# stm32f030f4p6_breakout.net
KiCad netlist of a schematic drawn in EAGLE
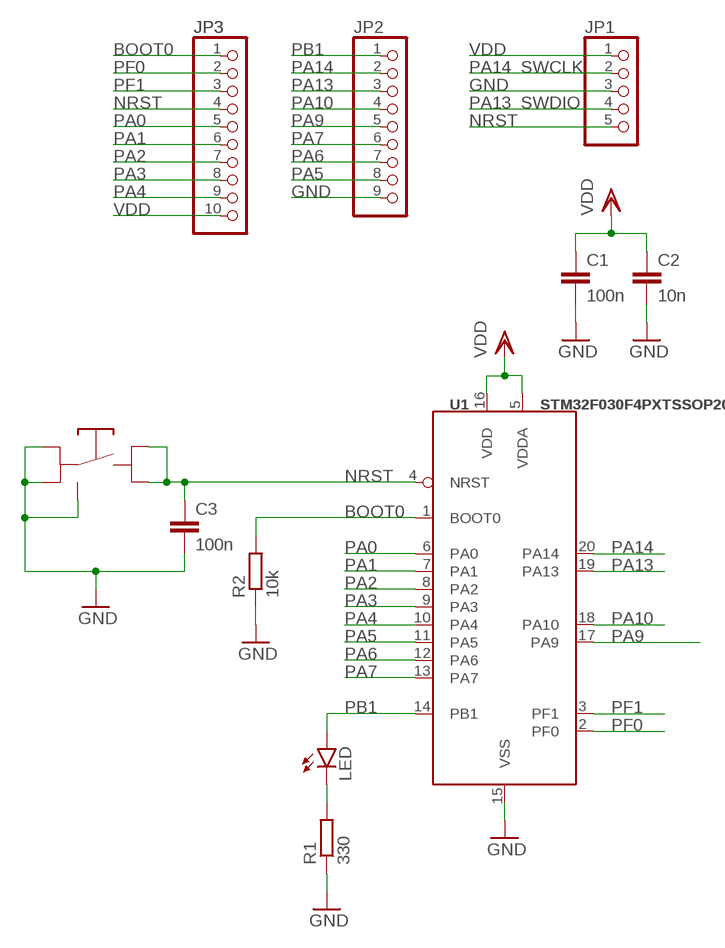
[diagram p0: schematic, sheet 1]

(export (version "E")
  (design (tool "Eeschema 10.0.6"))
  (components
    (comp (ref "C1")
      (value "100n")
      (footprint "eagle-import:C0603")
      (libsource (lib "eagle-import") (part "C-EUC0603"))
    )
    (comp (ref "C2")
      (value "10n")
      (footprint "eagle-import:C0603")
      (libsource (lib "eagle-import") (part "C-EUC0603"))
    )
    (comp (ref "C3")
      (value "100n")
      (footprint "eagle-import:C0603")
      (libsource (lib "eagle-import") (part "C-EUC0603"))
    )
    (comp (ref "JP1")
      (value "PINHD-1X5/90")
      (footprint "eagle-import:1X05_90")
      (libsource (lib "eagle-import") (part "PINHD-1X5/90"))
    )
    (comp (ref "JP2")
      (value "PINHD-1X9")
      (footprint "eagle-import:1X09")
      (libsource (lib "eagle-import") (part "PINHD-1X9"))
    )
    (comp (ref "JP3")
      (value "PINHD-1X10")
      (footprint "eagle-import:1X10")
      (libsource (lib "eagle-import") (part "PINHD-1X10"))
    )
    (comp (ref "LED")
      (value "LED")
      (footprint "eagle-import:LED-0603-CR")
      (libsource (lib "eagle-import") (part "LED"))
    )
    (comp (ref "R1")
      (value "330")
      (footprint "eagle-import:R0603")
      (libsource (lib "eagle-import") (part "R-EUR0603"))
    )
    (comp (ref "R2")
      (value "10k")
      (footprint "eagle-import:R0603")
      (libsource (lib "eagle-import") (part "R-EUR0603"))
    )
    (comp (ref "RESET")
      (value "KMR2XXG")
      (footprint "eagle-import:KMR2XXG")
      (libsource (lib "eagle-import") (part "KMR2XXG"))
    )
    (comp (ref "U1")
      (value "STM32F030F4PXTSSOP20")
      (footprint "eagle-import:STM32F030F4PX_TSSOP20")
      (libsource (lib "eagle-import") (part "STM32F030F4PXTSSOP20"))
    )
  )
  (nets
    (net (code "1") (name "/BOOT0") (class "Default")
      (node (ref "JP3") (pin "1") (pinfunction "1_1") (pintype "passive"))
      (node (ref "R2") (pin "2") (pinfunction "2_2") (pintype "passive"))
      (node (ref "U1") (pin "1") (pinfunction "BOOT0_1") (pintype "input"))
    )
    (net (code "2") (name "/NRST") (class "Default")
      (node (ref "C3") (pin "1") (pinfunction "1_1") (pintype "passive"))
      (node (ref "JP1") (pin "5") (pinfunction "5_5") (pintype "passive"))
      (node (ref "JP3") (pin "4") (pinfunction "4_4") (pintype "passive"))
      (node (ref "RESET") (pin "P$1") (pinfunction "1_P$1") (pintype "bidirectional"))
      (node (ref "RESET") (pin "P$2") (pinfunction "2_P$2") (pintype "bidirectional"))
      (node (ref "U1") (pin "4") (pinfunction "NRST_4") (pintype "input"))
    )
    (net (code "3") (name "/PA0") (class "Default")
      (node (ref "JP3") (pin "5") (pinfunction "5_5") (pintype "passive"))
      (node (ref "U1") (pin "6") (pinfunction "PA0_6") (pintype "bidirectional"))
    )
    (net (code "4") (name "/PA1") (class "Default")
      (node (ref "JP3") (pin "6") (pinfunction "6_6") (pintype "passive"))
      (node (ref "U1") (pin "7") (pinfunction "PA1_7") (pintype "bidirectional"))
    )
    (net (code "5") (name "/PA2") (class "Default")
      (node (ref "JP3") (pin "7") (pinfunction "7_7") (pintype "passive"))
      (node (ref "U1") (pin "8") (pinfunction "PA2_8") (pintype "bidirectional"))
    )
    (net (code "6") (name "/PA3") (class "Default")
      (node (ref "JP3") (pin "8") (pinfunction "8_8") (pintype "passive"))
      (node (ref "U1") (pin "9") (pinfunction "PA3_9") (pintype "bidirectional"))
    )
    (net (code "7") (name "/PA4") (class "Default")
      (node (ref "JP3") (pin "9") (pinfunction "9_9") (pintype "passive"))
      (node (ref "U1") (pin "10") (pinfunction "PA4_10") (pintype "bidirectional"))
    )
    (net (code "8") (name "/PA5") (class "Default")
      (node (ref "JP2") (pin "8") (pinfunction "8_8") (pintype "passive"))
      (node (ref "U1") (pin "11") (pinfunction "PA5_11") (pintype "bidirectional"))
    )
    (net (code "9") (name "/PA6") (class "Default")
      (node (ref "JP2") (pin "7") (pinfunction "7_7") (pintype "passive"))
      (node (ref "U1") (pin "12") (pinfunction "PA6_12") (pintype "bidirectional"))
    )
    (net (code "10") (name "/PA7") (class "Default")
      (node (ref "JP2") (pin "6") (pinfunction "6_6") (pintype "passive"))
      (node (ref "U1") (pin "13") (pinfunction "PA7_13") (pintype "bidirectional"))
    )
    (net (code "11") (name "/PA9") (class "Default")
      (node (ref "JP2") (pin "5") (pinfunction "5_5") (pintype "passive"))
      (node (ref "U1") (pin "17") (pinfunction "PA9_17") (pintype "bidirectional"))
    )
    (net (code "12") (name "/PA10") (class "Default")
      (node (ref "JP2") (pin "4") (pinfunction "4_4") (pintype "passive"))
      (node (ref "U1") (pin "18") (pinfunction "PA10_18") (pintype "bidirectional"))
    )
    (net (code "13") (name "/PA13") (class "Default")
      (node (ref "JP1") (pin "4") (pinfunction "4_4") (pintype "passive"))
      (node (ref "JP2") (pin "3") (pinfunction "3_3") (pintype "passive"))
      (node (ref "U1") (pin "19") (pinfunction "PA13_19") (pintype "bidirectional"))
    )
    (net (code "14") (name "/PA14") (class "Default")
      (node (ref "JP1") (pin "2") (pinfunction "2_2") (pintype "passive"))
      (node (ref "JP2") (pin "2") (pinfunction "2_2") (pintype "passive"))
      (node (ref "U1") (pin "20") (pinfunction "PA14_20") (pintype "bidirectional"))
    )
    (net (code "15") (name "/PB1") (class "Default")
      (node (ref "JP2") (pin "1") (pinfunction "1_1") (pintype "passive"))
      (node (ref "LED") (pin "2") (pinfunction "A_2") (pintype "passive"))
      (node (ref "U1") (pin "14") (pinfunction "PB1_14") (pintype "bidirectional"))
    )
    (net (code "16") (name "/PF0") (class "Default")
      (node (ref "JP3") (pin "2") (pinfunction "2_2") (pintype "passive"))
      (node (ref "U1") (pin "2") (pinfunction "PF0_2") (pintype "bidirectional"))
    )
    (net (code "17") (name "/PF1") (class "Default")
      (node (ref "JP3") (pin "3") (pinfunction "3_3") (pintype "passive"))
      (node (ref "U1") (pin "3") (pinfunction "PF1_3") (pintype "bidirectional"))
    )
    (net (code "18") (name "GND") (class "Default")
      (node (ref "C1") (pin "2") (pinfunction "2_2") (pintype "passive"))
      (node (ref "C2") (pin "2") (pinfunction "2_2") (pintype "passive"))
      (node (ref "C3") (pin "2") (pinfunction "2_2") (pintype "passive"))
      (node (ref "JP1") (pin "3") (pinfunction "3_3") (pintype "passive"))
      (node (ref "JP2") (pin "9") (pinfunction "9_9") (pintype "passive"))
      (node (ref "R1") (pin "1") (pinfunction "1_1") (pintype "passive"))
      (node (ref "R2") (pin "1") (pinfunction "1_1") (pintype "passive"))
      (node (ref "RESET") (pin "P$3") (pinfunction "3_P$3") (pintype "bidirectional"))
      (node (ref "RESET") (pin "P$4") (pinfunction "4_P$4") (pintype "bidirectional"))
      (node (ref "RESET") (pin "P$5") (pinfunction "G_P$5") (pintype "bidirectional"))
      (node (ref "U1") (pin "15") (pinfunction "VSS_15") (pintype "power_in"))
    )
    (net (code "19") (name "Net-(LED-C)") (class "Default")
      (node (ref "LED") (pin "1") (pinfunction "C_1") (pintype "passive"))
      (node (ref "R1") (pin "2") (pinfunction "2_2") (pintype "passive"))
    )
    (net (code "20") (name "VDD") (class "Default")
      (node (ref "C1") (pin "1") (pinfunction "1_1") (pintype "passive"))
      (node (ref "C2") (pin "1") (pinfunction "1_1") (pintype "passive"))
      (node (ref "JP1") (pin "1") (pinfunction "1_1") (pintype "passive"))
      (node (ref "JP3") (pin "10") (pinfunction "10_10") (pintype "passive"))
      (node (ref "U1") (pin "16") (pinfunction "VDD_16") (pintype "power_in"))
      (node (ref "U1") (pin "5") (pinfunction "VDDA_5") (pintype "power_in"))
    )
  )
)
